# cotroler.net
KiCad netlist of a schematic drawn in EAGLE
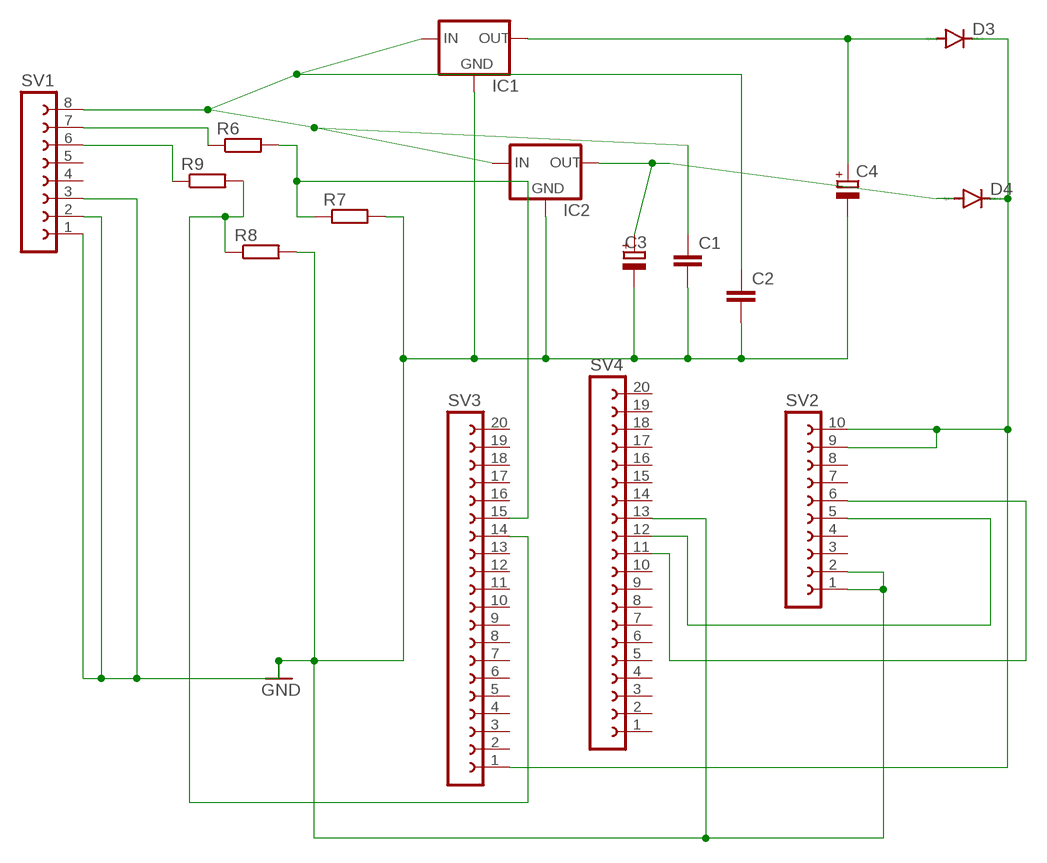
[diagram p0: schematic, sheet 1]

(export (version "E")
  (design (tool "Eeschema 10.0.6"))
  (components
    (comp (ref "C1")
      (value "C-EU025-024X044")
      (footprint "eagle-import:C025-024X044")
      (libsource (lib "eagle-import") (part "C-EU025-024X044"))
    )
    (comp (ref "C2")
      (value "C-EU025-024X044")
      (footprint "eagle-import:C025-024X044")
      (libsource (lib "eagle-import") (part "C-EU025-024X044"))
    )
    (comp (ref "C3")
      (value "CPOL-EUE2.5-5")
      (footprint "eagle-import:E2,5-5")
      (libsource (lib "eagle-import") (part "CPOL-EUE2.5-5"))
    )
    (comp (ref "C4")
      (value "CPOL-EUE2.5-5")
      (footprint "eagle-import:E2,5-5")
      (libsource (lib "eagle-import") (part "CPOL-EUE2.5-5"))
    )
    (comp (ref "D3")
      (value "DIODE-D-10")
      (footprint "eagle-import:D-10")
      (libsource (lib "eagle-import") (part "DIODE-D-10"))
    )
    (comp (ref "D4")
      (value "DIODE-D-10")
      (footprint "eagle-import:D-10")
      (libsource (lib "eagle-import") (part "DIODE-D-10"))
    )
    (comp (ref "IC1")
      (value "78XXS")
      (footprint "eagle-import:78XXS")
      (libsource (lib "eagle-import") (part "78XXS"))
    )
    (comp (ref "IC2")
      (value "78XXS")
      (footprint "eagle-import:78XXS")
      (libsource (lib "eagle-import") (part "78XXS"))
    )
    (comp (ref "R6")
      (value "R-EU_0207/10")
      (footprint "eagle-import:0207_10")
      (libsource (lib "eagle-import") (part "R-EU_0207/10"))
    )
    (comp (ref "R7")
      (value "R-EU_0207/10")
      (footprint "eagle-import:0207_10")
      (libsource (lib "eagle-import") (part "R-EU_0207/10"))
    )
    (comp (ref "R8")
      (value "R-EU_0207/10")
      (footprint "eagle-import:0207_10")
      (libsource (lib "eagle-import") (part "R-EU_0207/10"))
    )
    (comp (ref "R9")
      (value "R-EU_0207/10")
      (footprint "eagle-import:0207_10")
      (libsource (lib "eagle-import") (part "R-EU_0207/10"))
    )
    (comp (ref "SV1")
      (value "FE08-1")
      (footprint "eagle-import:FE08")
      (libsource (lib "eagle-import") (part "FE08-1"))
    )
    (comp (ref "SV2")
      (value "FE10-1")
      (footprint "eagle-import:FE10")
      (libsource (lib "eagle-import") (part "FE10-1"))
    )
    (comp (ref "SV3")
      (value "FE20-1")
      (footprint "eagle-import:FE20")
      (libsource (lib "eagle-import") (part "FE20-1"))
    )
    (comp (ref "SV4")
      (value "FE20-1")
      (footprint "eagle-import:FE20")
      (libsource (lib "eagle-import") (part "FE20-1"))
    )
  )
  (nets
    (net (code "1") (name "GND") (class "Default")
      (node (ref "C1") (pin "2") (pinfunction "2_2") (pintype "passive"))
      (node (ref "C2") (pin "2") (pinfunction "2_2") (pintype "passive"))
      (node (ref "C3") (pin "-") (pinfunction "-_-") (pintype "passive"))
      (node (ref "C4") (pin "-") (pinfunction "-_-") (pintype "passive"))
      (node (ref "IC1") (pin "GND") (pinfunction "GND_GND") (pintype "input"))
      (node (ref "IC2") (pin "GND") (pinfunction "GND_GND") (pintype "input"))
      (node (ref "R7") (pin "2") (pinfunction "2_2") (pintype "passive"))
      (node (ref "R8") (pin "2") (pinfunction "2_2") (pintype "passive"))
      (node (ref "SV1") (pin "1") (pinfunction "1_1") (pintype "passive"))
      (node (ref "SV1") (pin "2") (pinfunction "2_2") (pintype "passive"))
      (node (ref "SV1") (pin "3") (pinfunction "3_3") (pintype "passive"))
      (node (ref "SV2") (pin "1") (pinfunction "1_1") (pintype "passive"))
      (node (ref "SV2") (pin "2") (pinfunction "2_2") (pintype "passive"))
      (node (ref "SV4") (pin "13") (pinfunction "13_13") (pintype "passive"))
    )
    (net (code "2") (name "Net-(C1-Pad1)") (class "Default")
      (node (ref "C1") (pin "1") (pinfunction "1_1") (pintype "passive"))
      (node (ref "C2") (pin "1") (pinfunction "1_1") (pintype "passive"))
      (node (ref "IC1") (pin "IN") (pinfunction "IN_IN") (pintype "input"))
      (node (ref "IC2") (pin "IN") (pinfunction "IN_IN") (pintype "input"))
      (node (ref "SV1") (pin "8") (pinfunction "8_8") (pintype "passive"))
    )
    (net (code "3") (name "Net-(C3-Pad+)") (class "Default")
      (node (ref "C3") (pin "+") (pinfunction "+_+") (pintype "passive"))
      (node (ref "D4") (pin "A") (pinfunction "A_A") (pintype "passive"))
      (node (ref "IC2") (pin "OUT") (pinfunction "OUT_OUT") (pintype "passive"))
    )
    (net (code "4") (name "Net-(C4-Pad+)") (class "Default")
      (node (ref "C4") (pin "+") (pinfunction "+_+") (pintype "passive"))
      (node (ref "D3") (pin "A") (pinfunction "A_A") (pintype "passive"))
      (node (ref "IC1") (pin "OUT") (pinfunction "OUT_OUT") (pintype "passive"))
    )
    (net (code "5") (name "Net-(D3-PadC)") (class "Default")
      (node (ref "D3") (pin "C") (pinfunction "C_C") (pintype "passive"))
      (node (ref "D4") (pin "C") (pinfunction "C_C") (pintype "passive"))
      (node (ref "SV2") (pin "10") (pinfunction "10_10") (pintype "passive"))
      (node (ref "SV2") (pin "9") (pinfunction "9_9") (pintype "passive"))
      (node (ref "SV3") (pin "1") (pinfunction "1_1") (pintype "passive"))
    )
    (net (code "6") (name "Net-(R6-Pad1)") (class "Default")
      (node (ref "R6") (pin "1") (pinfunction "1_1") (pintype "passive"))
      (node (ref "SV1") (pin "7") (pinfunction "7_7") (pintype "passive"))
    )
    (net (code "7") (name "Net-(R6-Pad2)") (class "Default")
      (node (ref "R6") (pin "2") (pinfunction "2_2") (pintype "passive"))
      (node (ref "R7") (pin "1") (pinfunction "1_1") (pintype "passive"))
      (node (ref "SV3") (pin "15") (pinfunction "15_15") (pintype "passive"))
    )
    (net (code "8") (name "Net-(R8-Pad1)") (class "Default")
      (node (ref "R8") (pin "1") (pinfunction "1_1") (pintype "passive"))
      (node (ref "R9") (pin "2") (pinfunction "2_2") (pintype "passive"))
      (node (ref "SV3") (pin "14") (pinfunction "14_14") (pintype "passive"))
    )
    (net (code "9") (name "Net-(R9-Pad1)") (class "Default")
      (node (ref "R9") (pin "1") (pinfunction "1_1") (pintype "passive"))
      (node (ref "SV1") (pin "6") (pinfunction "6_6") (pintype "passive"))
    )
    (net (code "10") (name "Net-(SV2-Pad5)") (class "Default")
      (node (ref "SV2") (pin "5") (pinfunction "5_5") (pintype "passive"))
      (node (ref "SV4") (pin "12") (pinfunction "12_12") (pintype "passive"))
    )
    (net (code "11") (name "Net-(SV2-Pad6)") (class "Default")
      (node (ref "SV2") (pin "6") (pinfunction "6_6") (pintype "passive"))
      (node (ref "SV4") (pin "11") (pinfunction "11_11") (pintype "passive"))
    )
    (net (code "12") (name "unconnected-(SV1-Pad4)") (class "Default")
      (node (ref "SV1") (pin "4") (pinfunction "4_4") (pintype "passive"))
    )
    (net (code "13") (name "unconnected-(SV1-Pad5)") (class "Default")
      (node (ref "SV1") (pin "5") (pinfunction "5_5") (pintype "passive"))
    )
    (net (code "14") (name "unconnected-(SV2-Pad3)") (class "Default")
      (node (ref "SV2") (pin "3") (pinfunction "3_3") (pintype "passive"))
    )
    (net (code "15") (name "unconnected-(SV2-Pad4)") (class "Default")
      (node (ref "SV2") (pin "4") (pinfunction "4_4") (pintype "passive"))
    )
    (net (code "16") (name "unconnected-(SV2-Pad7)") (class "Default")
      (node (ref "SV2") (pin "7") (pinfunction "7_7") (pintype "passive"))
    )
    (net (code "17") (name "unconnected-(SV2-Pad8)") (class "Default")
      (node (ref "SV2") (pin "8") (pinfunction "8_8") (pintype "passive"))
    )
    (net (code "18") (name "unconnected-(SV3-Pad2)") (class "Default")
      (node (ref "SV3") (pin "2") (pinfunction "2_2") (pintype "passive"))
    )
    (net (code "19") (name "unconnected-(SV3-Pad3)") (class "Default")
      (node (ref "SV3") (pin "3") (pinfunction "3_3") (pintype "passive"))
    )
    (net (code "20") (name "unconnected-(SV3-Pad4)") (class "Default")
      (node (ref "SV3") (pin "4") (pinfunction "4_4") (pintype "passive"))
    )
    (net (code "21") (name "unconnected-(SV3-Pad5)") (class "Default")
      (node (ref "SV3") (pin "5") (pinfunction "5_5") (pintype "passive"))
    )
    (net (code "22") (name "unconnected-(SV3-Pad6)") (class "Default")
      (node (ref "SV3") (pin "6") (pinfunction "6_6") (pintype "passive"))
    )
    (net (code "23") (name "unconnected-(SV3-Pad7)") (class "Default")
      (node (ref "SV3") (pin "7") (pinfunction "7_7") (pintype "passive"))
    )
    (net (code "24") (name "unconnected-(SV3-Pad8)") (class "Default")
      (node (ref "SV3") (pin "8") (pinfunction "8_8") (pintype "passive"))
    )
    (net (code "25") (name "unconnected-(SV3-Pad9)") (class "Default")
      (node (ref "SV3") (pin "9") (pinfunction "9_9") (pintype "passive"))
    )
    (net (code "26") (name "unconnected-(SV3-Pad10)") (class "Default")
      (node (ref "SV3") (pin "10") (pinfunction "10_10") (pintype "passive"))
    )
    (net (code "27") (name "unconnected-(SV3-Pad11)") (class "Default")
      (node (ref "SV3") (pin "11") (pinfunction "11_11") (pintype "passive"))
    )
    (net (code "28") (name "unconnected-(SV3-Pad12)") (class "Default")
      (node (ref "SV3") (pin "12") (pinfunction "12_12") (pintype "passive"))
    )
    (net (code "29") (name "unconnected-(SV3-Pad13)") (class "Default")
      (node (ref "SV3") (pin "13") (pinfunction "13_13") (pintype "passive"))
    )
    (net (code "30") (name "unconnected-(SV3-Pad16)") (class "Default")
      (node (ref "SV3") (pin "16") (pinfunction "16_16") (pintype "passive"))
    )
    (net (code "31") (name "unconnected-(SV3-Pad17)") (class "Default")
      (node (ref "SV3") (pin "17") (pinfunction "17_17") (pintype "passive"))
    )
    (net (code "32") (name "unconnected-(SV3-Pad18)") (class "Default")
      (node (ref "SV3") (pin "18") (pinfunction "18_18") (pintype "passive"))
    )
    (net (code "33") (name "unconnected-(SV3-Pad19)") (class "Default")
      (node (ref "SV3") (pin "19") (pinfunction "19_19") (pintype "passive"))
    )
    (net (code "34") (name "unconnected-(SV3-Pad20)") (class "Default")
      (node (ref "SV3") (pin "20") (pinfunction "20_20") (pintype "passive"))
    )
    (net (code "35") (name "unconnected-(SV4-Pad1)") (class "Default")
      (node (ref "SV4") (pin "1") (pinfunction "1_1") (pintype "passive"))
    )
    (net (code "36") (name "unconnected-(SV4-Pad2)") (class "Default")
      (node (ref "SV4") (pin "2") (pinfunction "2_2") (pintype "passive"))
    )
    (net (code "37") (name "unconnected-(SV4-Pad3)") (class "Default")
      (node (ref "SV4") (pin "3") (pinfunction "3_3") (pintype "passive"))
    )
    (net (code "38") (name "unconnected-(SV4-Pad4)") (class "Default")
      (node (ref "SV4") (pin "4") (pinfunction "4_4") (pintype "passive"))
    )
    (net (code "39") (name "unconnected-(SV4-Pad5)") (class "Default")
      (node (ref "SV4") (pin "5") (pinfunction "5_5") (pintype "passive"))
    )
    (net (code "40") (name "unconnected-(SV4-Pad6)") (class "Default")
      (node (ref "SV4") (pin "6") (pinfunction "6_6") (pintype "passive"))
    )
    (net (code "41") (name "unconnected-(SV4-Pad7)") (class "Default")
      (node (ref "SV4") (pin "7") (pinfunction "7_7") (pintype "passive"))
    )
    (net (code "42") (name "unconnected-(SV4-Pad8)") (class "Default")
      (node (ref "SV4") (pin "8") (pinfunction "8_8") (pintype "passive"))
    )
    (net (code "43") (name "unconnected-(SV4-Pad9)") (class "Default")
      (node (ref "SV4") (pin "9") (pinfunction "9_9") (pintype "passive"))
    )
    (net (code "44") (name "unconnected-(SV4-Pad10)") (class "Default")
      (node (ref "SV4") (pin "10") (pinfunction "10_10") (pintype "passive"))
    )
    (net (code "45") (name "unconnected-(SV4-Pad14)") (class "Default")
      (node (ref "SV4") (pin "14") (pinfunction "14_14") (pintype "passive"))
    )
    (net (code "46") (name "unconnected-(SV4-Pad15)") (class "Default")
      (node (ref "SV4") (pin "15") (pinfunction "15_15") (pintype "passive"))
    )
    (net (code "47") (name "unconnected-(SV4-Pad16)") (class "Default")
      (node (ref "SV4") (pin "16") (pinfunction "16_16") (pintype "passive"))
    )
    (net (code "48") (name "unconnected-(SV4-Pad17)") (class "Default")
      (node (ref "SV4") (pin "17") (pinfunction "17_17") (pintype "passive"))
    )
    (net (code "49") (name "unconnected-(SV4-Pad18)") (class "Default")
      (node (ref "SV4") (pin "18") (pinfunction "18_18") (pintype "passive"))
    )
    (net (code "50") (name "unconnected-(SV4-Pad19)") (class "Default")
      (node (ref "SV4") (pin "19") (pinfunction "19_19") (pintype "passive"))
    )
    (net (code "51") (name "unconnected-(SV4-Pad20)") (class "Default")
      (node (ref "SV4") (pin "20") (pinfunction "20_20") (pintype "passive"))
    )
  )
)
